# Key-HT16K33.net
KiCad netlist of a schematic drawn in Altium Designer
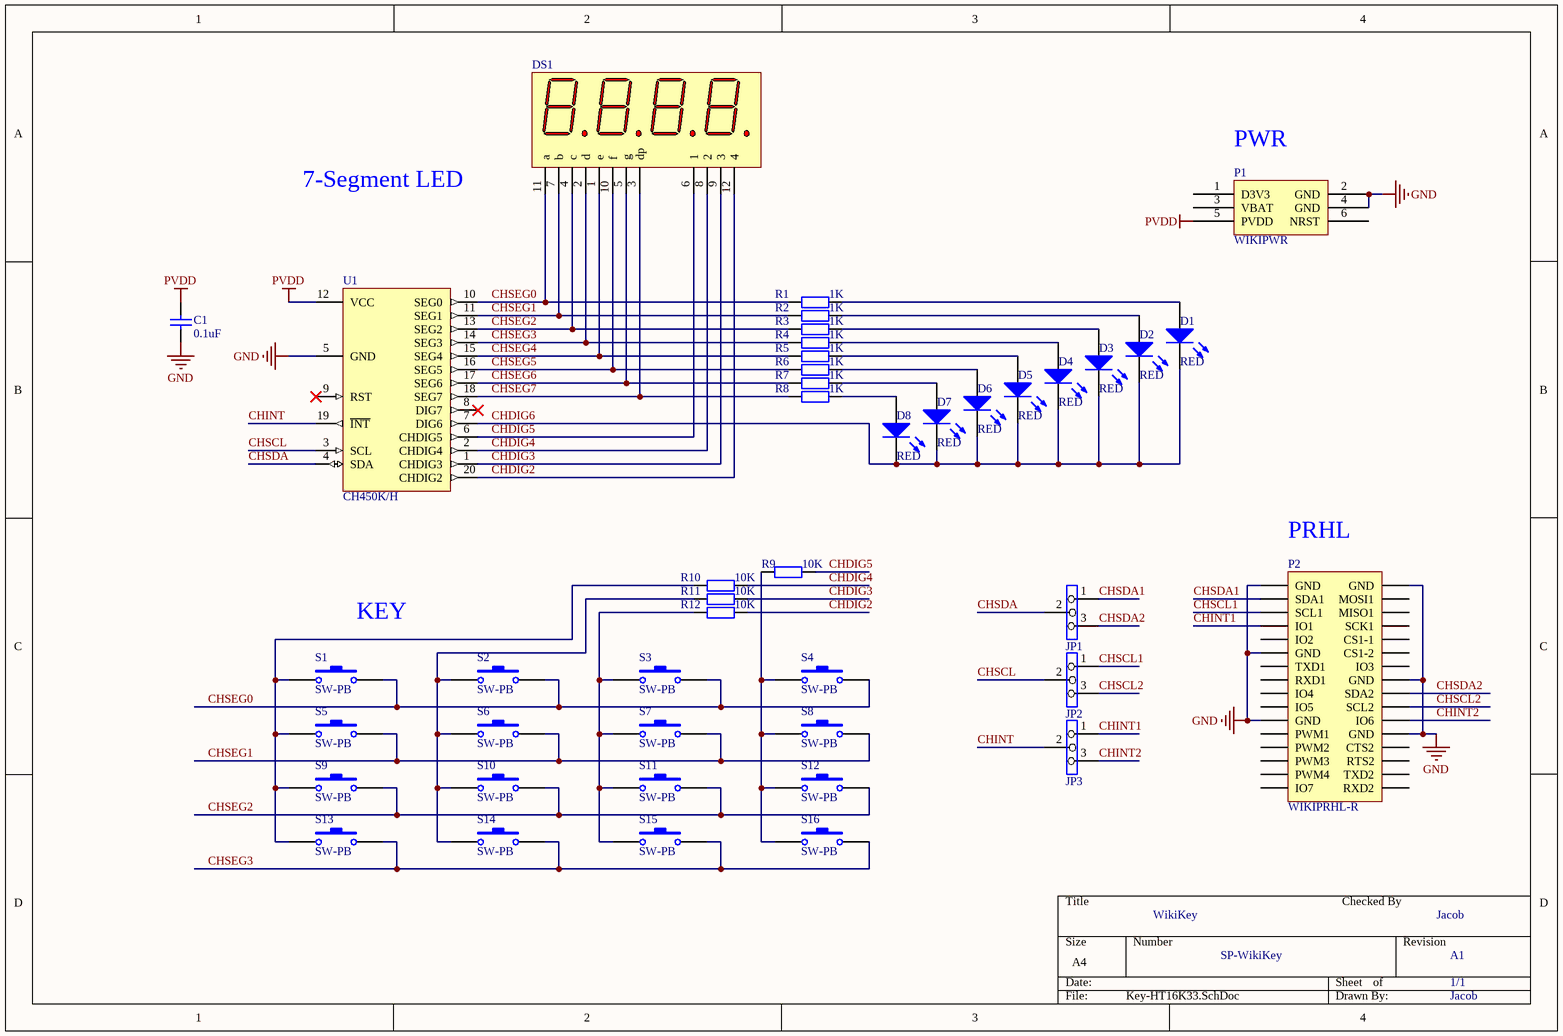
[diagram p0: Key-HT16K33.SchDoc]

(export (version "E")
  (design (tool "Eeschema 10.0.6"))
  (components
    (comp (ref "C1")
      (value "0.1uF")
      (footprint "0603M")
      (description "Capacitor")
      (fields (field (name "PUBLISHER") "Altium Limited"))
      (libsource (lib "Miscellaneous Devices") (part "Cap"))
    )
    (comp (ref "D1")
      (value "RED")
      (footprint "0603pn")
      (description "Typical INFRARED GaAs LED")
      (fields (field (name "PUBLISHER") "Altium Limited"))
      (libsource (lib "Miscellaneous Devices") (part "LED0"))
    )
    (comp (ref "D2")
      (value "RED")
      (footprint "0603pn")
      (description "Typical INFRARED GaAs LED")
      (fields (field (name "PUBLISHER") "Altium Limited"))
      (libsource (lib "Miscellaneous Devices") (part "LED0"))
    )
    (comp (ref "D3")
      (value "RED")
      (footprint "0603pn")
      (description "Typical INFRARED GaAs LED")
      (fields (field (name "PUBLISHER") "Altium Limited"))
      (libsource (lib "Miscellaneous Devices") (part "LED0"))
    )
    (comp (ref "D4")
      (value "RED")
      (footprint "0603pn")
      (description "Typical INFRARED GaAs LED")
      (fields (field (name "PUBLISHER") "Altium Limited"))
      (libsource (lib "Miscellaneous Devices") (part "LED0"))
    )
    (comp (ref "D5")
      (value "RED")
      (footprint "0603pn")
      (description "Typical INFRARED GaAs LED")
      (fields (field (name "PUBLISHER") "Altium Limited"))
      (libsource (lib "Miscellaneous Devices") (part "LED0"))
    )
    (comp (ref "D6")
      (value "RED")
      (footprint "0603pn")
      (description "Typical INFRARED GaAs LED")
      (fields (field (name "PUBLISHER") "Altium Limited"))
      (libsource (lib "Miscellaneous Devices") (part "LED0"))
    )
    (comp (ref "D7")
      (value "RED")
      (footprint "0603pn")
      (description "Typical INFRARED GaAs LED")
      (fields (field (name "PUBLISHER") "Altium Limited"))
      (libsource (lib "Miscellaneous Devices") (part "LED0"))
    )
    (comp (ref "D8")
      (value "RED")
      (footprint "0603pn")
      (description "Typical INFRARED GaAs LED")
      (fields (field (name "PUBLISHER") "Altium Limited"))
      (libsource (lib "Miscellaneous Devices") (part "LED0"))
    )
    (comp (ref "DS1")
      (value "7SEG-4")
      (footprint "7SGLED-4-0.28")
      (description "Black Surface HER 7-Segment Display")
      (fields (field (name "PUBLISHER") "Altium Limited"))
      (libsource (lib "Misc") (part "7SEG-4"))
    )
    (comp (ref "JP1") (value "Jumper3") (footprint "HDR1X3/2.54MM") (libsource (lib "Misc") (part "Jumper3")))
    (comp (ref "JP2") (value "Jumper3") (footprint "HDR1X3/2.54MM") (libsource (lib "Misc") (part "Jumper3")))
    (comp (ref "JP3") (value "Jumper3") (footprint "HDR1X3/2.54MM") (libsource (lib "Misc") (part "Jumper3")))
    (comp (ref "P1")
      (value "WIKIPWR")
      (footprint "WIKIPWR")
      (description "PWR HDR")
      (libsource (lib "Connector") (part "WIKIPWR"))
    )
    (comp (ref "P2")
      (value "WIKIPRHL-R")
      (footprint "HDR2X16-WIKIPRHL-R")
      (description "Header, 16-Pin, Dual row")
      (fields (field (name "PUBLISHER") "Altium Limited"))
      (libsource (lib "Connector") (part "WIKIPRHL-R"))
    )
    (comp (ref "R1")
      (value "1K")
      (footprint "0603M")
      (description "Resistor")
      (fields (field (name "PUBLISHER") "Altium Limited"))
      (libsource (lib "Miscellaneous Devices") (part "Res2"))
    )
    (comp (ref "R2")
      (value "1K")
      (footprint "0603M")
      (description "Resistor")
      (fields (field (name "PUBLISHER") "Altium Limited"))
      (libsource (lib "Miscellaneous Devices") (part "Res2"))
    )
    (comp (ref "R3")
      (value "1K")
      (footprint "0603M")
      (description "Resistor")
      (fields (field (name "PUBLISHER") "Altium Limited"))
      (libsource (lib "Miscellaneous Devices") (part "Res2"))
    )
    (comp (ref "R4")
      (value "1K")
      (footprint "0603M")
      (description "Resistor")
      (fields (field (name "PUBLISHER") "Altium Limited"))
      (libsource (lib "Miscellaneous Devices") (part "Res2"))
    )
    (comp (ref "R5")
      (value "1K")
      (footprint "0603M")
      (description "Resistor")
      (fields (field (name "PUBLISHER") "Altium Limited"))
      (libsource (lib "Miscellaneous Devices") (part "Res2"))
    )
    (comp (ref "R6")
      (value "1K")
      (footprint "0603M")
      (description "Resistor")
      (fields (field (name "PUBLISHER") "Altium Limited"))
      (libsource (lib "Miscellaneous Devices") (part "Res2"))
    )
    (comp (ref "R7")
      (value "1K")
      (footprint "0603M")
      (description "Resistor")
      (fields (field (name "PUBLISHER") "Altium Limited"))
      (libsource (lib "Miscellaneous Devices") (part "Res2"))
    )
    (comp (ref "R8")
      (value "1K")
      (footprint "0603M")
      (description "Resistor")
      (fields (field (name "PUBLISHER") "Altium Limited"))
      (libsource (lib "Miscellaneous Devices") (part "Res2"))
    )
    (comp (ref "R9")
      (value "10K")
      (footprint "0603M")
      (description "Resistor")
      (fields (field (name "PUBLISHER") "Altium Limited"))
      (libsource (lib "Miscellaneous Devices") (part "Res2"))
    )
    (comp (ref "R10")
      (value "10K")
      (footprint "0603M")
      (description "Resistor")
      (fields (field (name "PUBLISHER") "Altium Limited"))
      (libsource (lib "Miscellaneous Devices") (part "Res2"))
    )
    (comp (ref "R11")
      (value "10K")
      (footprint "0603M")
      (description "Resistor")
      (fields (field (name "PUBLISHER") "Altium Limited"))
      (libsource (lib "Miscellaneous Devices") (part "Res2"))
    )
    (comp (ref "R12")
      (value "10K")
      (footprint "0603M")
      (description "Resistor")
      (fields (field (name "PUBLISHER") "Altium Limited"))
      (libsource (lib "Miscellaneous Devices") (part "Res2"))
    )
    (comp (ref "S1")
      (value "SW-PB")
      (footprint "KEY-4.5X4.5-SMD")
      (description "Switch")
      (fields (field (name "PUBLISHER") "Altium Limited"))
      (libsource (lib "CT107D_SUDA") (part "SW-PB"))
    )
    (comp (ref "S2")
      (value "SW-PB")
      (footprint "KEY-4.5X4.5-SMD")
      (description "Switch")
      (fields (field (name "PUBLISHER") "Altium Limited"))
      (libsource (lib "CT107D_SUDA") (part "SW-PB"))
    )
    (comp (ref "S3")
      (value "SW-PB")
      (footprint "KEY-4.5X4.5-SMD")
      (description "Switch")
      (fields (field (name "PUBLISHER") "Altium Limited"))
      (libsource (lib "CT107D_SUDA") (part "SW-PB"))
    )
    (comp (ref "S4")
      (value "SW-PB")
      (footprint "KEY-4.5X4.5-SMD")
      (description "Switch")
      (fields (field (name "PUBLISHER") "Altium Limited"))
      (libsource (lib "CT107D_SUDA") (part "SW-PB"))
    )
    (comp (ref "S5")
      (value "SW-PB")
      (footprint "KEY-4.5X4.5-SMD")
      (description "Switch")
      (fields (field (name "PUBLISHER") "Altium Limited"))
      (libsource (lib "CT107D_SUDA") (part "SW-PB"))
    )
    (comp (ref "S6")
      (value "SW-PB")
      (footprint "KEY-4.5X4.5-SMD")
      (description "Switch")
      (fields (field (name "PUBLISHER") "Altium Limited"))
      (libsource (lib "CT107D_SUDA") (part "SW-PB"))
    )
    (comp (ref "S7")
      (value "SW-PB")
      (footprint "KEY-4.5X4.5-SMD")
      (description "Switch")
      (fields (field (name "PUBLISHER") "Altium Limited"))
      (libsource (lib "CT107D_SUDA") (part "SW-PB"))
    )
    (comp (ref "S8")
      (value "SW-PB")
      (footprint "KEY-4.5X4.5-SMD")
      (description "Switch")
      (fields (field (name "PUBLISHER") "Altium Limited"))
      (libsource (lib "CT107D_SUDA") (part "SW-PB"))
    )
    (comp (ref "S9")
      (value "SW-PB")
      (footprint "KEY-4.5X4.5-SMD")
      (description "Switch")
      (fields (field (name "PUBLISHER") "Altium Limited"))
      (libsource (lib "CT107D_SUDA") (part "SW-PB"))
    )
    (comp (ref "S10")
      (value "SW-PB")
      (footprint "KEY-4.5X4.5-SMD")
      (description "Switch")
      (fields (field (name "PUBLISHER") "Altium Limited"))
      (libsource (lib "CT107D_SUDA") (part "SW-PB"))
    )
    (comp (ref "S11")
      (value "SW-PB")
      (footprint "KEY-4.5X4.5-SMD")
      (description "Switch")
      (fields (field (name "PUBLISHER") "Altium Limited"))
      (libsource (lib "CT107D_SUDA") (part "SW-PB"))
    )
    (comp (ref "S12")
      (value "SW-PB")
      (footprint "KEY-4.5X4.5-SMD")
      (description "Switch")
      (fields (field (name "PUBLISHER") "Altium Limited"))
      (libsource (lib "CT107D_SUDA") (part "SW-PB"))
    )
    (comp (ref "S13")
      (value "SW-PB")
      (footprint "KEY-4.5X4.5-SMD")
      (description "Switch")
      (fields (field (name "PUBLISHER") "Altium Limited"))
      (libsource (lib "CT107D_SUDA") (part "SW-PB"))
    )
    (comp (ref "S14")
      (value "SW-PB")
      (footprint "KEY-4.5X4.5-SMD")
      (description "Switch")
      (fields (field (name "PUBLISHER") "Altium Limited"))
      (libsource (lib "CT107D_SUDA") (part "SW-PB"))
    )
    (comp (ref "S15")
      (value "SW-PB")
      (footprint "KEY-4.5X4.5-SMD")
      (description "Switch")
      (fields (field (name "PUBLISHER") "Altium Limited"))
      (libsource (lib "CT107D_SUDA") (part "SW-PB"))
    )
    (comp (ref "S16")
      (value "SW-PB")
      (footprint "KEY-4.5X4.5-SMD")
      (description "Switch")
      (fields (field (name "PUBLISHER") "Altium Limited"))
      (libsource (lib "CT107D_SUDA") (part "SW-PB"))
    )
    (comp (ref "U1")
      (value "CH450K/H")
      (footprint "SO20W_M")
      (description "7 Segment LED& Key")
      (libsource (lib "Lunio") (part "CH450K/H"))
    )
  )
  (nets
    (net (code "1") (name "/CHDIG2") (class "Default")
      (node (ref "DS1") (pin "12") (pinfunction "4_12") (pintype "passive"))
      (node (ref "R12") (pin "1") (pinfunction "1_1") (pintype "passive"))
      (node (ref "U1") (pin "20") (pinfunction "CHDIG2_20") (pintype "output"))
    )
    (net (code "2") (name "/CHDIG3") (class "Default")
      (node (ref "DS1") (pin "9") (pinfunction "3_9") (pintype "passive"))
      (node (ref "R11") (pin "1") (pinfunction "1_1") (pintype "passive"))
      (node (ref "U1") (pin "1") (pinfunction "CHDIG3_1") (pintype "output"))
    )
    (net (code "3") (name "/CHDIG4") (class "Default")
      (node (ref "DS1") (pin "8") (pinfunction "2_8") (pintype "passive"))
      (node (ref "R10") (pin "1") (pinfunction "1_1") (pintype "passive"))
      (node (ref "U1") (pin "2") (pinfunction "CHDIG4_2") (pintype "output"))
    )
    (net (code "4") (name "/CHDIG5") (class "Default")
      (node (ref "DS1") (pin "6") (pinfunction "1_6") (pintype "passive"))
      (node (ref "R9") (pin "1") (pinfunction "1_1") (pintype "passive"))
      (node (ref "U1") (pin "6") (pinfunction "CHDIG5_6") (pintype "output"))
    )
    (net (code "5") (name "/CHDIG6") (class "Default")
      (node (ref "D1") (pin "2") (pinfunction "K_2") (pintype "passive"))
      (node (ref "D2") (pin "2") (pinfunction "K_2") (pintype "passive"))
      (node (ref "D3") (pin "2") (pinfunction "K_2") (pintype "passive"))
      (node (ref "D4") (pin "2") (pinfunction "K_2") (pintype "passive"))
      (node (ref "D5") (pin "2") (pinfunction "K_2") (pintype "passive"))
      (node (ref "D6") (pin "2") (pinfunction "K_2") (pintype "passive"))
      (node (ref "D7") (pin "2") (pinfunction "K_2") (pintype "passive"))
      (node (ref "D8") (pin "2") (pinfunction "K_2") (pintype "passive"))
      (node (ref "U1") (pin "7") (pinfunction "DIG6_7") (pintype "output"))
    )
    (net (code "6") (name "/CHINT") (class "Default")
      (node (ref "JP3") (pin "2") (pintype "passive"))
      (node (ref "U1") (pin "19") (pinfunction "~{INT}_19") (pintype "output"))
    )
    (net (code "7") (name "/CHINT1") (class "Default")
      (node (ref "JP3") (pin "1") (pintype "passive"))
      (node (ref "P2") (pin "7") (pinfunction "IO1_7") (pintype "passive"))
    )
    (net (code "8") (name "/CHINT2") (class "Default")
      (node (ref "JP3") (pin "3") (pintype "passive"))
      (node (ref "P2") (pin "22") (pinfunction "IO6_22") (pintype "passive"))
    )
    (net (code "9") (name "/CHSCL") (class "Default")
      (node (ref "JP2") (pin "2") (pintype "passive"))
      (node (ref "U1") (pin "3") (pinfunction "SCL_3") (pintype "input"))
    )
    (net (code "10") (name "/CHSCL1") (class "Default")
      (node (ref "JP2") (pin "1") (pintype "passive"))
      (node (ref "P2") (pin "5") (pinfunction "SCL1_5") (pintype "passive"))
    )
    (net (code "11") (name "/CHSCL2") (class "Default")
      (node (ref "JP2") (pin "3") (pintype "passive"))
      (node (ref "P2") (pin "20") (pinfunction "SCL2_20") (pintype "passive"))
    )
    (net (code "12") (name "/CHSDA") (class "Default")
      (node (ref "JP1") (pin "2") (pintype "passive"))
      (node (ref "U1") (pin "4") (pinfunction "SDA_4") (pintype "bidirectional"))
    )
    (net (code "13") (name "/CHSDA1") (class "Default")
      (node (ref "JP1") (pin "1") (pintype "passive"))
      (node (ref "P2") (pin "3") (pinfunction "SDA1_3") (pintype "passive"))
    )
    (net (code "14") (name "/CHSDA2") (class "Default")
      (node (ref "JP1") (pin "3") (pintype "passive"))
      (node (ref "P2") (pin "18") (pinfunction "SDA2_18") (pintype "passive"))
    )
    (net (code "15") (name "/CHSEG0") (class "Default")
      (node (ref "DS1") (pin "11") (pinfunction "a_11") (pintype "passive"))
      (node (ref "R1") (pin "2") (pinfunction "2_2") (pintype "passive"))
      (node (ref "S1") (pin "2") (pinfunction "2_2") (pintype "passive"))
      (node (ref "S2") (pin "2") (pinfunction "2_2") (pintype "passive"))
      (node (ref "S3") (pin "2") (pinfunction "2_2") (pintype "passive"))
      (node (ref "S4") (pin "2") (pinfunction "2_2") (pintype "passive"))
      (node (ref "U1") (pin "10") (pinfunction "SEG0_10") (pintype "output"))
    )
    (net (code "16") (name "/CHSEG1") (class "Default")
      (node (ref "DS1") (pin "7") (pinfunction "b_7") (pintype "passive"))
      (node (ref "R2") (pin "2") (pinfunction "2_2") (pintype "passive"))
      (node (ref "S5") (pin "2") (pinfunction "2_2") (pintype "passive"))
      (node (ref "S6") (pin "2") (pinfunction "2_2") (pintype "passive"))
      (node (ref "S7") (pin "2") (pinfunction "2_2") (pintype "passive"))
      (node (ref "S8") (pin "2") (pinfunction "2_2") (pintype "passive"))
      (node (ref "U1") (pin "11") (pinfunction "SEG1_11") (pintype "output"))
    )
    (net (code "17") (name "/CHSEG2") (class "Default")
      (node (ref "DS1") (pin "4") (pinfunction "c_4") (pintype "passive"))
      (node (ref "R3") (pin "2") (pinfunction "2_2") (pintype "passive"))
      (node (ref "S10") (pin "2") (pinfunction "2_2") (pintype "passive"))
      (node (ref "S11") (pin "2") (pinfunction "2_2") (pintype "passive"))
      (node (ref "S12") (pin "2") (pinfunction "2_2") (pintype "passive"))
      (node (ref "S9") (pin "2") (pinfunction "2_2") (pintype "passive"))
      (node (ref "U1") (pin "13") (pinfunction "SEG2_13") (pintype "output"))
    )
    (net (code "18") (name "/CHSEG3") (class "Default")
      (node (ref "DS1") (pin "2") (pinfunction "d_2") (pintype "passive"))
      (node (ref "R4") (pin "2") (pinfunction "2_2") (pintype "passive"))
      (node (ref "S13") (pin "2") (pinfunction "2_2") (pintype "passive"))
      (node (ref "S14") (pin "2") (pinfunction "2_2") (pintype "passive"))
      (node (ref "S15") (pin "2") (pinfunction "2_2") (pintype "passive"))
      (node (ref "S16") (pin "2") (pinfunction "2_2") (pintype "passive"))
      (node (ref "U1") (pin "14") (pinfunction "SEG3_14") (pintype "output"))
    )
    (net (code "19") (name "/CHSEG4") (class "Default")
      (node (ref "DS1") (pin "1") (pinfunction "e_1") (pintype "passive"))
      (node (ref "R5") (pin "2") (pinfunction "2_2") (pintype "passive"))
      (node (ref "U1") (pin "15") (pinfunction "SEG4_15") (pintype "output"))
    )
    (net (code "20") (name "/CHSEG5") (class "Default")
      (node (ref "DS1") (pin "10") (pinfunction "f_10") (pintype "passive"))
      (node (ref "R6") (pin "2") (pinfunction "2_2") (pintype "passive"))
      (node (ref "U1") (pin "16") (pinfunction "SEG5_16") (pintype "output"))
    )
    (net (code "21") (name "/CHSEG6") (class "Default")
      (node (ref "DS1") (pin "5") (pinfunction "g_5") (pintype "passive"))
      (node (ref "R7") (pin "2") (pinfunction "2_2") (pintype "passive"))
      (node (ref "U1") (pin "17") (pinfunction "SEG6_17") (pintype "output"))
    )
    (net (code "22") (name "/CHSEG7") (class "Default")
      (node (ref "DS1") (pin "3") (pinfunction "dp_3") (pintype "passive"))
      (node (ref "R8") (pin "2") (pinfunction "2_2") (pintype "passive"))
      (node (ref "U1") (pin "18") (pinfunction "SEG7_18") (pintype "output"))
    )
    (net (code "23") (name "GND") (class "Default")
      (node (ref "C1") (pin "1") (pinfunction "1_1") (pintype "passive"))
      (node (ref "P1") (pin "2") (pinfunction "GND_2") (pintype "passive"))
      (node (ref "P1") (pin "4") (pinfunction "GND_4") (pintype "passive"))
      (node (ref "P2") (pin "1") (pinfunction "GND_1") (pintype "passive"))
      (node (ref "P2") (pin "11") (pinfunction "GND_11") (pintype "passive"))
      (node (ref "P2") (pin "16") (pinfunction "GND_16") (pintype "passive"))
      (node (ref "P2") (pin "2") (pinfunction "GND_2") (pintype "passive"))
      (node (ref "P2") (pin "21") (pinfunction "GND_21") (pintype "passive"))
      (node (ref "P2") (pin "24") (pinfunction "GND_24") (pintype "passive"))
      (node (ref "U1") (pin "5") (pinfunction "GND_5") (pintype "power_in"))
    )
    (net (code "24") (name "Net-(D1-A)") (class "Default")
      (node (ref "D1") (pin "1") (pinfunction "A_1") (pintype "passive"))
      (node (ref "R1") (pin "1") (pinfunction "1_1") (pintype "passive"))
    )
    (net (code "25") (name "Net-(D2-A)") (class "Default")
      (node (ref "D2") (pin "1") (pinfunction "A_1") (pintype "passive"))
      (node (ref "R2") (pin "1") (pinfunction "1_1") (pintype "passive"))
    )
    (net (code "26") (name "Net-(D3-A)") (class "Default")
      (node (ref "D3") (pin "1") (pinfunction "A_1") (pintype "passive"))
      (node (ref "R3") (pin "1") (pinfunction "1_1") (pintype "passive"))
    )
    (net (code "27") (name "Net-(D4-A)") (class "Default")
      (node (ref "D4") (pin "1") (pinfunction "A_1") (pintype "passive"))
      (node (ref "R4") (pin "1") (pinfunction "1_1") (pintype "passive"))
    )
    (net (code "28") (name "Net-(D5-A)") (class "Default")
      (node (ref "D5") (pin "1") (pinfunction "A_1") (pintype "passive"))
      (node (ref "R5") (pin "1") (pinfunction "1_1") (pintype "passive"))
    )
    (net (code "29") (name "Net-(D6-A)") (class "Default")
      (node (ref "D6") (pin "1") (pinfunction "A_1") (pintype "passive"))
      (node (ref "R6") (pin "1") (pinfunction "1_1") (pintype "passive"))
    )
    (net (code "30") (name "Net-(D7-A)") (class "Default")
      (node (ref "D7") (pin "1") (pinfunction "A_1") (pintype "passive"))
      (node (ref "R7") (pin "1") (pinfunction "1_1") (pintype "passive"))
    )
    (net (code "31") (name "Net-(D8-A)") (class "Default")
      (node (ref "D8") (pin "1") (pinfunction "A_1") (pintype "passive"))
      (node (ref "R8") (pin "1") (pinfunction "1_1") (pintype "passive"))
    )
    (net (code "32") (name "Net-(R9-Pad2)") (class "Default")
      (node (ref "R9") (pin "2") (pinfunction "2_2") (pintype "passive"))
      (node (ref "S12") (pin "1") (pinfunction "1_1") (pintype "passive"))
      (node (ref "S16") (pin "1") (pinfunction "1_1") (pintype "passive"))
      (node (ref "S4") (pin "1") (pinfunction "1_1") (pintype "passive"))
      (node (ref "S8") (pin "1") (pinfunction "1_1") (pintype "passive"))
    )
    (net (code "33") (name "Net-(R10-Pad2)") (class "Default")
      (node (ref "R10") (pin "2") (pinfunction "2_2") (pintype "passive"))
      (node (ref "S1") (pin "1") (pinfunction "1_1") (pintype "passive"))
      (node (ref "S13") (pin "1") (pinfunction "1_1") (pintype "passive"))
      (node (ref "S5") (pin "1") (pinfunction "1_1") (pintype "passive"))
      (node (ref "S9") (pin "1") (pinfunction "1_1") (pintype "passive"))
    )
    (net (code "34") (name "Net-(R11-Pad2)") (class "Default")
      (node (ref "R11") (pin "2") (pinfunction "2_2") (pintype "passive"))
      (node (ref "S10") (pin "1") (pinfunction "1_1") (pintype "passive"))
      (node (ref "S14") (pin "1") (pinfunction "1_1") (pintype "passive"))
      (node (ref "S2") (pin "1") (pinfunction "1_1") (pintype "passive"))
      (node (ref "S6") (pin "1") (pinfunction "1_1") (pintype "passive"))
    )
    (net (code "35") (name "Net-(R12-Pad2)") (class "Default")
      (node (ref "R12") (pin "2") (pinfunction "2_2") (pintype "passive"))
      (node (ref "S11") (pin "1") (pinfunction "1_1") (pintype "passive"))
      (node (ref "S15") (pin "1") (pinfunction "1_1") (pintype "passive"))
      (node (ref "S3") (pin "1") (pinfunction "1_1") (pintype "passive"))
      (node (ref "S7") (pin "1") (pinfunction "1_1") (pintype "passive"))
    )
    (net (code "36") (name "PVDD") (class "Default")
      (node (ref "C1") (pin "2") (pinfunction "2_2") (pintype "passive"))
      (node (ref "P1") (pin "5") (pinfunction "PVDD_5") (pintype "passive"))
      (node (ref "U1") (pin "12") (pinfunction "VCC_12") (pintype "power_in"))
    )
    (net (code "37") (name "unconnected-(P1-D3V3-Pad1)") (class "Default")
      (node (ref "P1") (pin "1") (pinfunction "D3V3_1") (pintype "passive"))
    )
    (net (code "38") (name "unconnected-(P1-NRST-Pad6)") (class "Default")
      (node (ref "P1") (pin "6") (pinfunction "NRST_6") (pintype "passive"))
    )
    (net (code "39") (name "unconnected-(P1-VBAT-Pad3)") (class "Default")
      (node (ref "P1") (pin "3") (pinfunction "VBAT_3") (pintype "passive"))
    )
    (net (code "40") (name "unconnected-(P2-CS1-1-Pad10)") (class "Default")
      (node (ref "P2") (pin "10") (pinfunction "CS1-1_10") (pintype "passive"))
    )
    (net (code "41") (name "unconnected-(P2-CS1-2-Pad12)") (class "Default")
      (node (ref "P2") (pin "12") (pinfunction "CS1-2_12") (pintype "passive"))
    )
    (net (code "42") (name "unconnected-(P2-CTS2-Pad26)") (class "Default")
      (node (ref "P2") (pin "26") (pinfunction "CTS2_26") (pintype "passive"))
    )
    (net (code "43") (name "unconnected-(P2-IO2-Pad9)") (class "Default")
      (node (ref "P2") (pin "9") (pinfunction "IO2_9") (pintype "passive"))
    )
    (net (code "44") (name "unconnected-(P2-IO3-Pad14)") (class "Default")
      (node (ref "P2") (pin "14") (pinfunction "IO3_14") (pintype "passive"))
    )
    (net (code "45") (name "unconnected-(P2-IO4-Pad17)") (class "Default")
      (node (ref "P2") (pin "17") (pinfunction "IO4_17") (pintype "passive"))
    )
    (net (code "46") (name "unconnected-(P2-IO5-Pad19)") (class "Default")
      (node (ref "P2") (pin "19") (pinfunction "IO5_19") (pintype "passive"))
    )
    (net (code "47") (name "unconnected-(P2-IO7-Pad31)") (class "Default")
      (node (ref "P2") (pin "31") (pinfunction "IO7_31") (pintype "passive"))
    )
    (net (code "48") (name "unconnected-(P2-MISO1-Pad6)") (class "Default")
      (node (ref "P2") (pin "6") (pinfunction "MISO1_6") (pintype "passive"))
    )
    (net (code "49") (name "unconnected-(P2-MOSI1-Pad4)") (class "Default")
      (node (ref "P2") (pin "4") (pinfunction "MOSI1_4") (pintype "passive"))
    )
    (net (code "50") (name "unconnected-(P2-PWM1-Pad23)") (class "Default")
      (node (ref "P2") (pin "23") (pinfunction "PWM1_23") (pintype "passive"))
    )
    (net (code "51") (name "unconnected-(P2-PWM2-Pad25)") (class "Default")
      (node (ref "P2") (pin "25") (pinfunction "PWM2_25") (pintype "passive"))
    )
    (net (code "52") (name "unconnected-(P2-PWM3-Pad27)") (class "Default")
      (node (ref "P2") (pin "27") (pinfunction "PWM3_27") (pintype "passive"))
    )
    (net (code "53") (name "unconnected-(P2-PWM4-Pad29)") (class "Default")
      (node (ref "P2") (pin "29") (pinfunction "PWM4_29") (pintype "passive"))
    )
    (net (code "54") (name "unconnected-(P2-RTS2-Pad28)") (class "Default")
      (node (ref "P2") (pin "28") (pinfunction "RTS2_28") (pintype "passive"))
    )
    (net (code "55") (name "unconnected-(P2-RXD1-Pad15)") (class "Default")
      (node (ref "P2") (pin "15") (pinfunction "RXD1_15") (pintype "passive"))
    )
    (net (code "56") (name "unconnected-(P2-RXD2-Pad32)") (class "Default")
      (node (ref "P2") (pin "32") (pinfunction "RXD2_32") (pintype "passive"))
    )
    (net (code "57") (name "unconnected-(P2-SCK1-Pad8)") (class "Default")
      (node (ref "P2") (pin "8") (pinfunction "SCK1_8") (pintype "passive"))
    )
    (net (code "58") (name "unconnected-(P2-TXD1-Pad13)") (class "Default")
      (node (ref "P2") (pin "13") (pinfunction "TXD1_13") (pintype "passive"))
    )
    (net (code "59") (name "unconnected-(P2-TXD2-Pad30)") (class "Default")
      (node (ref "P2") (pin "30") (pinfunction "TXD2_30") (pintype "passive"))
    )
    (net (code "60") (name "unconnected-(U1-DIG7-Pad8)") (class "Default")
      (node (ref "U1") (pin "8") (pinfunction "DIG7_8") (pintype "output+no_connect"))
    )
    (net (code "61") (name "unconnected-(U1-RST-Pad9)") (class "Default")
      (node (ref "U1") (pin "9") (pinfunction "RST_9") (pintype "input+no_connect"))
    )
  )
)
